# digital.net
KiCad netlist of a schematic drawn in Altium Designer
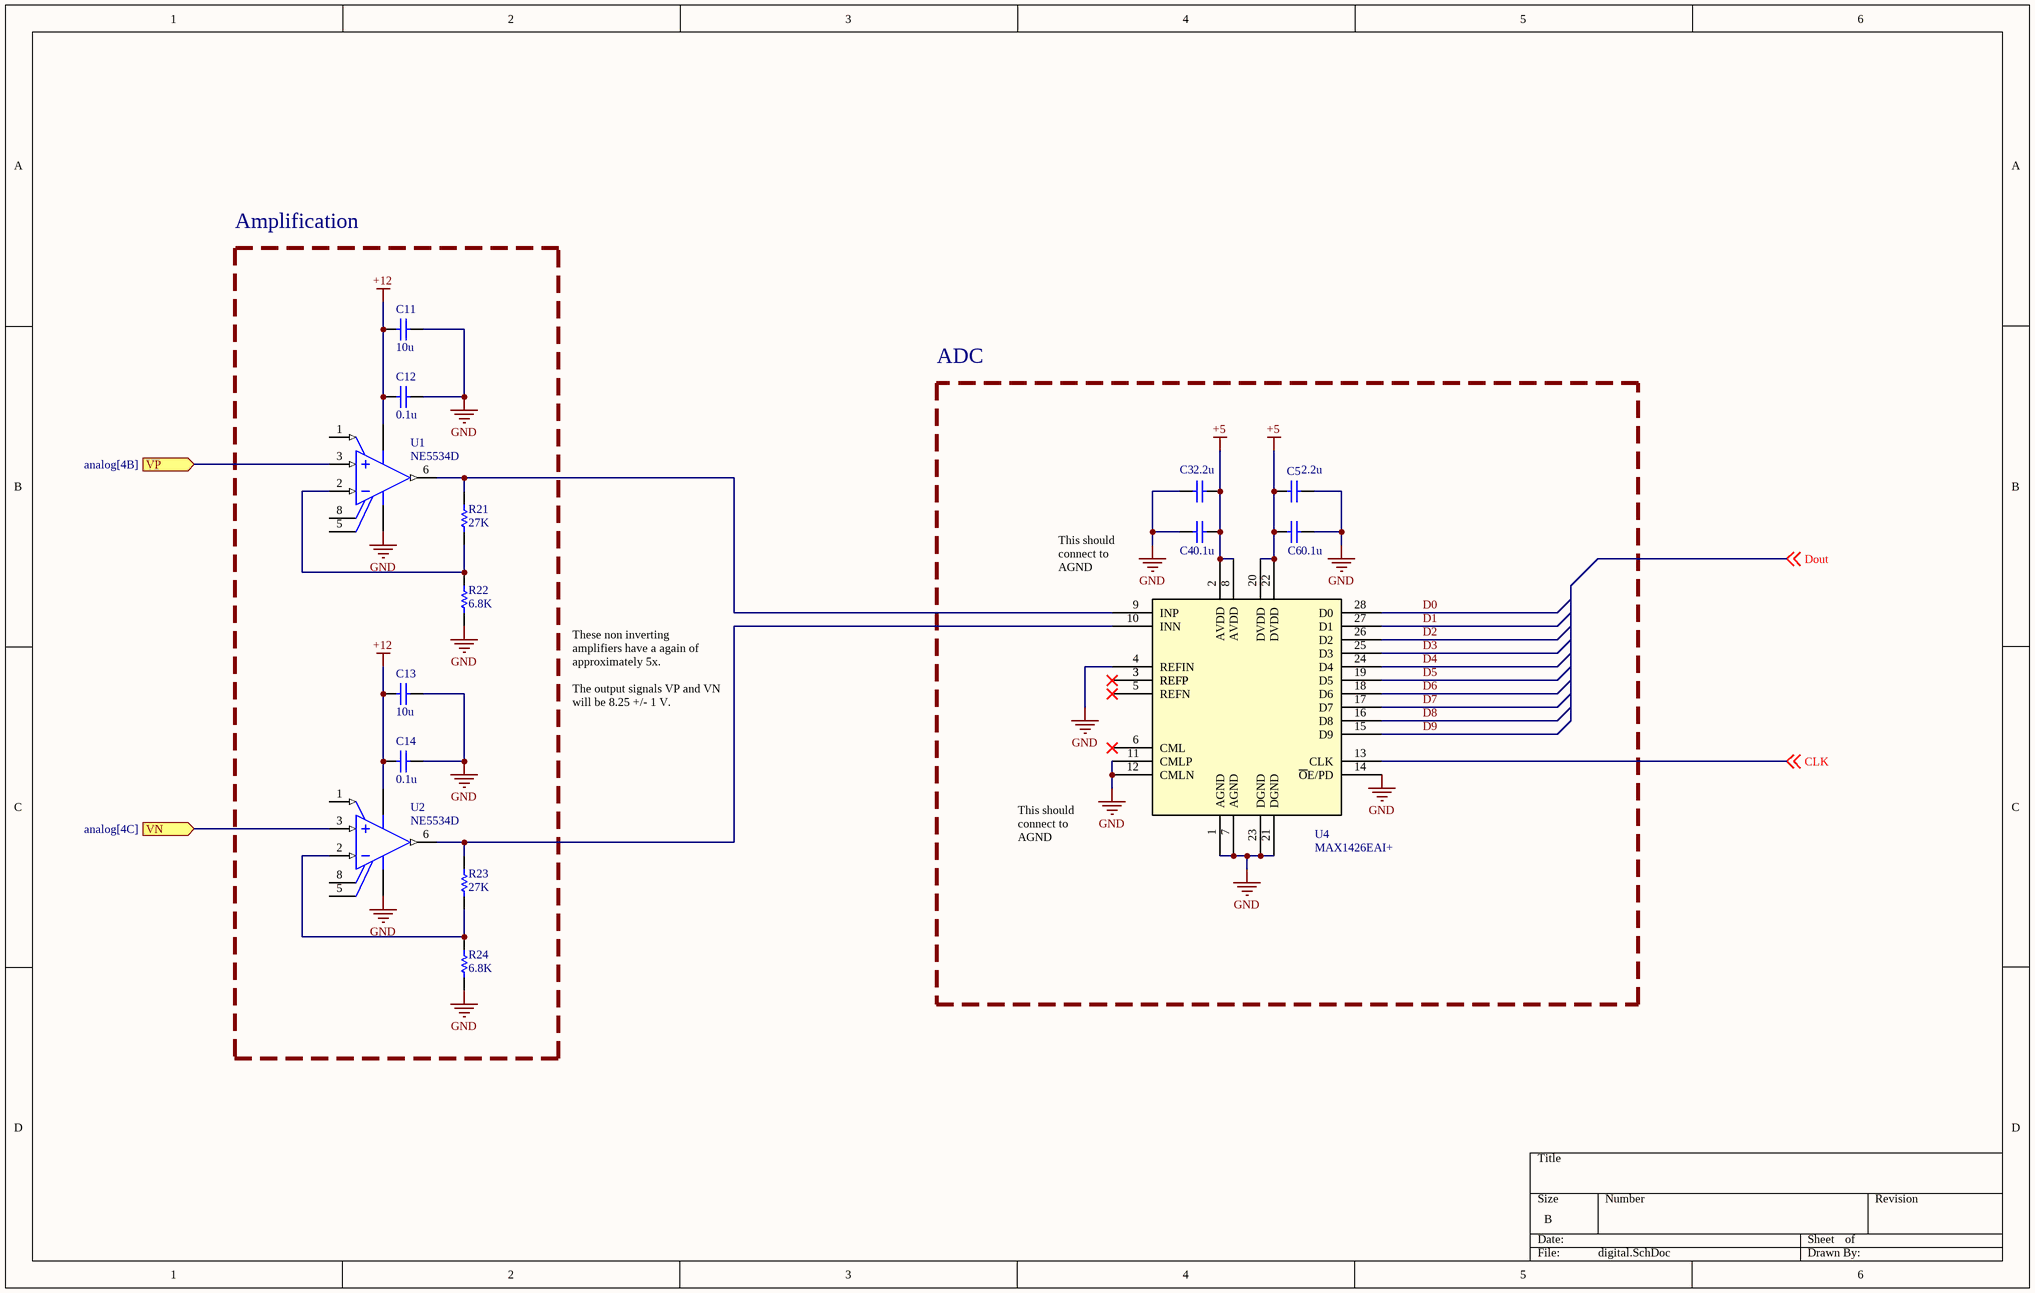
[diagram p0: digital.SchDoc]

(export (version "E")
  (design (tool "Eeschema 10.0.6"))
  (components
    (comp (ref "C3")
      (value "2.2u")
      (description "Capacitor")
      (libsource (lib "Simulation Generic Components") (part "Capacitor"))
    )
    (comp (ref "C4")
      (value "0.1u")
      (description "Capacitor")
      (libsource (lib "Simulation Generic Components") (part "Capacitor"))
    )
    (comp (ref "C5")
      (value "2.2u")
      (description "Capacitor")
      (libsource (lib "Simulation Generic Components") (part "Capacitor"))
    )
    (comp (ref "C6")
      (value "0.1u")
      (description "Capacitor")
      (libsource (lib "Simulation Generic Components") (part "Capacitor"))
    )
    (comp (ref "C11")
      (value "10u")
      (description "Capacitor")
      (libsource (lib "Simulation Generic Components") (part "Capacitor"))
    )
    (comp (ref "C12")
      (value "0.1u")
      (description "Capacitor")
      (libsource (lib "Simulation Generic Components") (part "Capacitor"))
    )
    (comp (ref "C13")
      (value "10u")
      (description "Capacitor")
      (libsource (lib "Simulation Generic Components") (part "Capacitor"))
    )
    (comp (ref "C14")
      (value "0.1u")
      (description "Capacitor")
      (libsource (lib "Simulation Generic Components") (part "Capacitor"))
    )
    (comp (ref "R21")
      (value "27K")
      (description "Resistor")
      (libsource (lib "Simulation Generic Components") (part "Resistor"))
    )
    (comp (ref "R22")
      (value "6.8K")
      (description "Resistor")
      (libsource (lib "Simulation Generic Components") (part "Resistor"))
    )
    (comp (ref "R23")
      (value "27K")
      (description "Resistor")
      (libsource (lib "Simulation Generic Components") (part "Resistor"))
    )
    (comp (ref "R24")
      (value "6.8K")
      (description "Resistor")
      (libsource (lib "Simulation Generic Components") (part "Resistor"))
    )
    (comp (ref "U1")
      (value "NE5534D")
      (footprint "D0008A_N")
      (fields (field (name "MANUFACTURER") "Texas Instruments"))
      (libsource (lib "Altium Content Vault") (part "TI-XX5534X-X8"))
    )
    (comp (ref "U2")
      (value "NE5534D")
      (footprint "D0008A_N")
      (fields (field (name "MANUFACTURER") "Texas Instruments"))
      (libsource (lib "Altium Content Vault") (part "TI-XX5534X-X8"))
    )
    (comp (ref "U4")
      (value "MAX1426EAI+")
      (footprint "21-0056C_28_MXM")
      (description "No Description Available")
      (libsource (lib "dvl") (part "MAX1426EAI+"))
    )
  )
  (nets
    (net (code "1") (name "+5") (class "Default")
      (node (ref "C3") (pin "2") (pinfunction "2_2") (pintype "passive"))
      (node (ref "C4") (pin "2") (pinfunction "2_2") (pintype "passive"))
      (node (ref "C5") (pin "2") (pinfunction "2_2") (pintype "passive"))
      (node (ref "C6") (pin "2") (pinfunction "2_2") (pintype "passive"))
      (node (ref "U4") (pin "2") (pinfunction "AVDD_2") (pintype "power_in"))
      (node (ref "U4") (pin "20") (pinfunction "DVDD_20") (pintype "power_in"))
      (node (ref "U4") (pin "22") (pinfunction "DVDD_22") (pintype "power_in"))
      (node (ref "U4") (pin "8") (pinfunction "AVDD_8") (pintype "power_in"))
    )
    (net (code "2") (name "+12") (class "Default")
      (node (ref "C11") (pin "1") (pinfunction "1_1") (pintype "passive"))
      (node (ref "C12") (pin "1") (pinfunction "1_1") (pintype "passive"))
      (node (ref "C13") (pin "1") (pinfunction "1_1") (pintype "passive"))
      (node (ref "C14") (pin "1") (pinfunction "1_1") (pintype "passive"))
      (node (ref "U1") (pin "4") (pinfunction "VCC-_4") (pintype "power_in"))
      (node (ref "U2") (pin "4") (pinfunction "VCC-_4") (pintype "power_in"))
    )
    (net (code "3") (name "/D0") (class "Default")
      (node (ref "U4") (pin "28") (pinfunction "D0_28") (pintype "passive"))
    )
    (net (code "4") (name "/D1") (class "Default")
      (node (ref "U4") (pin "27") (pinfunction "D1_27") (pintype "passive"))
    )
    (net (code "5") (name "/D2") (class "Default")
      (node (ref "U4") (pin "26") (pinfunction "D2_26") (pintype "passive"))
    )
    (net (code "6") (name "/D3") (class "Default")
      (node (ref "U4") (pin "25") (pinfunction "D3_25") (pintype "passive"))
    )
    (net (code "7") (name "/D4") (class "Default")
      (node (ref "U4") (pin "24") (pinfunction "D4_24") (pintype "passive"))
    )
    (net (code "8") (name "/D5") (class "Default")
      (node (ref "U4") (pin "19") (pinfunction "D5_19") (pintype "passive"))
    )
    (net (code "9") (name "/D6") (class "Default")
      (node (ref "U4") (pin "18") (pinfunction "D6_18") (pintype "passive"))
    )
    (net (code "10") (name "/D7") (class "Default")
      (node (ref "U4") (pin "17") (pinfunction "D7_17") (pintype "passive"))
    )
    (net (code "11") (name "/D8") (class "Default")
      (node (ref "U4") (pin "16") (pinfunction "D8_16") (pintype "passive"))
    )
    (net (code "12") (name "/D9") (class "Default")
      (node (ref "U4") (pin "15") (pinfunction "D9_15") (pintype "passive"))
    )
    (net (code "13") (name "/VN") (class "Default")
      (node (ref "U2") (pin "3") (pinfunction "IN+_3") (pintype "input"))
    )
    (net (code "14") (name "/VP") (class "Default")
      (node (ref "U1") (pin "3") (pinfunction "IN+_3") (pintype "input"))
    )
    (net (code "15") (name "CLK") (class "Default")
      (node (ref "U4") (pin "13") (pinfunction "CLK_13") (pintype "passive"))
    )
    (net (code "17") (name "GND") (class "Default")
      (node (ref "C11") (pin "2") (pinfunction "2_2") (pintype "passive"))
      (node (ref "C12") (pin "2") (pinfunction "2_2") (pintype "passive"))
      (node (ref "C13") (pin "2") (pinfunction "2_2") (pintype "passive"))
      (node (ref "C14") (pin "2") (pinfunction "2_2") (pintype "passive"))
      (node (ref "C3") (pin "1") (pinfunction "1_1") (pintype "passive"))
      (node (ref "C4") (pin "1") (pinfunction "1_1") (pintype "passive"))
      (node (ref "C5") (pin "1") (pinfunction "1_1") (pintype "passive"))
      (node (ref "C6") (pin "1") (pinfunction "1_1") (pintype "passive"))
      (node (ref "R22") (pin "1") (pinfunction "1_1") (pintype "passive"))
      (node (ref "R24") (pin "1") (pinfunction "1_1") (pintype "passive"))
      (node (ref "U1") (pin "7") (pinfunction "VCC+_7") (pintype "power_in"))
      (node (ref "U2") (pin "7") (pinfunction "VCC+_7") (pintype "power_in"))
      (node (ref "U4") (pin "1") (pinfunction "AGND_1") (pintype "power_in"))
      (node (ref "U4") (pin "11") (pinfunction "CMLP_11") (pintype "passive"))
      (node (ref "U4") (pin "12") (pinfunction "CMLN_12") (pintype "passive"))
      (node (ref "U4") (pin "14") (pinfunction "~{O}E/PD_14") (pintype "passive"))
      (node (ref "U4") (pin "21") (pinfunction "DGND_21") (pintype "power_in"))
      (node (ref "U4") (pin "23") (pinfunction "DGND_23") (pintype "power_in"))
      (node (ref "U4") (pin "4") (pinfunction "REFIN_4") (pintype "passive"))
      (node (ref "U4") (pin "7") (pinfunction "AGND_7") (pintype "power_in"))
    )
    (net (code "18") (name "Net-(U1-IN-)") (class "Default")
      (node (ref "R21") (pin "1") (pinfunction "1_1") (pintype "passive"))
      (node (ref "R22") (pin "2") (pinfunction "2_2") (pintype "passive"))
      (node (ref "U1") (pin "2") (pinfunction "IN-_2") (pintype "input"))
    )
    (net (code "19") (name "Net-(U1-OUT)") (class "Default")
      (node (ref "R21") (pin "2") (pinfunction "2_2") (pintype "passive"))
      (node (ref "U1") (pin "6") (pinfunction "OUT_6") (pintype "output"))
      (node (ref "U4") (pin "9") (pinfunction "INP_9") (pintype "passive"))
    )
    (net (code "20") (name "Net-(U2-IN-)") (class "Default")
      (node (ref "R23") (pin "1") (pinfunction "1_1") (pintype "passive"))
      (node (ref "R24") (pin "2") (pinfunction "2_2") (pintype "passive"))
      (node (ref "U2") (pin "2") (pinfunction "IN-_2") (pintype "input"))
    )
    (net (code "21") (name "Net-(U2-OUT)") (class "Default")
      (node (ref "R23") (pin "2") (pinfunction "2_2") (pintype "passive"))
      (node (ref "U2") (pin "6") (pinfunction "OUT_6") (pintype "output"))
      (node (ref "U4") (pin "10") (pinfunction "INN_10") (pintype "passive"))
    )
    (net (code "22") (name "unconnected-(U1-BALANCE-Pad1)") (class "Default")
      (node (ref "U1") (pin "1") (pinfunction "BALANCE_1") (pintype "input"))
    )
    (net (code "23") (name "unconnected-(U1-COMP-Pad5)") (class "Default")
      (node (ref "U1") (pin "5") (pinfunction "COMP_5") (pintype "passive"))
    )
    (net (code "24") (name "unconnected-(U1-COMP{slash}BAL-Pad8)") (class "Default")
      (node (ref "U1") (pin "8") (pinfunction "COMP/BAL_8") (pintype "passive"))
    )
    (net (code "25") (name "unconnected-(U2-BALANCE-Pad1)") (class "Default")
      (node (ref "U2") (pin "1") (pinfunction "BALANCE_1") (pintype "input"))
    )
    (net (code "26") (name "unconnected-(U2-COMP-Pad5)") (class "Default")
      (node (ref "U2") (pin "5") (pinfunction "COMP_5") (pintype "passive"))
    )
    (net (code "27") (name "unconnected-(U2-COMP{slash}BAL-Pad8)") (class "Default")
      (node (ref "U2") (pin "8") (pinfunction "COMP/BAL_8") (pintype "passive"))
    )
    (net (code "28") (name "unconnected-(U4-CML-Pad6)") (class "Default")
      (node (ref "U4") (pin "6") (pinfunction "CML_6") (pintype "passive+no_connect"))
    )
    (net (code "29") (name "unconnected-(U4-REFN-Pad5)") (class "Default")
      (node (ref "U4") (pin "5") (pinfunction "REFN_5") (pintype "passive+no_connect"))
    )
    (net (code "30") (name "unconnected-(U4-REFP-Pad3)") (class "Default")
      (node (ref "U4") (pin "3") (pinfunction "REFP_3") (pintype "passive+no_connect"))
    )
  )
)
